# Buzzer.net
KiCad netlist of a schematic drawn in Altium Designer
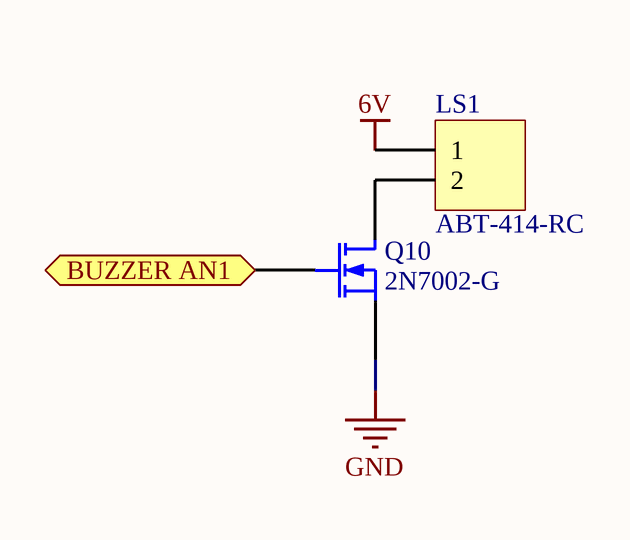
[diagram p0: Buzzer.SchDoc]

(export (version "E")
  (design (tool "Eeschema 10.0.6"))
  (components
    (comp (ref "LS1")
      (value "ABT-414-RC")
      (footprint "Buzzer")
      (description "Header, 2-Pin")
      (fields (field (name "PUBLISHER") "Altium Limited"))
      (libsource (lib "Miscellaneous Connectors") (part "Header 2"))
    )
    (comp (ref "Q10")
      (value "2N7002-G")
      (footprint "Mosfet")
      (description "N-Channel MOSFET")
      (fields (field (name "PUBLISHER") "Altium Limited"))
      (libsource (lib "Miscellaneous Devices") (part "MOSFET-N"))
    )
  )
  (nets
    (net (code "1") (name "/BUZZER AN1") (class "Default")
      (node (ref "Q10") (pin "1") (pinfunction "G_1") (pintype "passive"))
    )
    (net (code "2") (name "6V") (class "Default")
      (node (ref "LS1") (pin "1") (pinfunction "1_1") (pintype "passive"))
    )
    (net (code "3") (name "GND") (class "Default")
      (node (ref "Q10") (pin "2") (pinfunction "S_2") (pintype "passive"))
    )
    (net (code "4") (name "Net-(Q10-D)") (class "Default")
      (node (ref "LS1") (pin "2") (pinfunction "2_2") (pintype "passive"))
      (node (ref "Q10") (pin "3") (pinfunction "D_3") (pintype "passive"))
    )
  )
)
